# CommBoard.net
KiCad netlist of a schematic drawn in Altium Designer
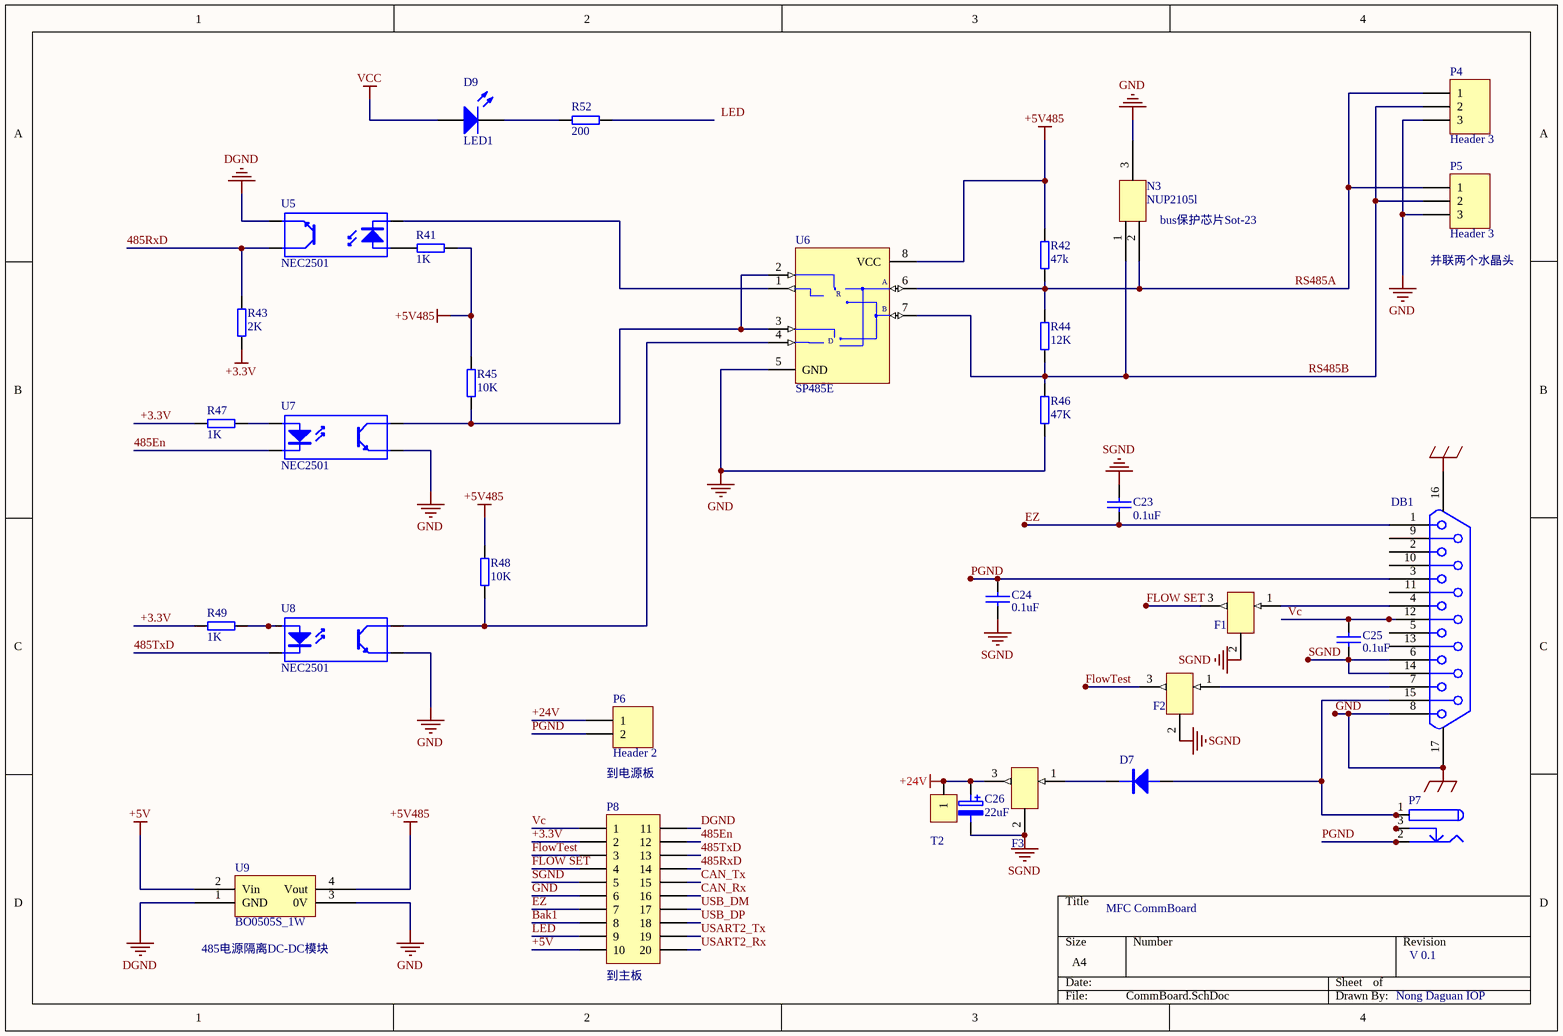
[diagram p0: CommBoard.SchDoc]

(export (version "E")
  (design (tool "Eeschema 10.0.6"))
  (components
    (comp (ref "C23") (value "0.1uF") (footprint "R.4") (libsource (lib "1.60") (part "CAP")))
    (comp (ref "C24") (value "0.1uF") (footprint "R.4") (libsource (lib "1.60") (part "CAP")))
    (comp (ref "C25") (value "0.1uF") (footprint "R.4") (libsource (lib "1.60") (part "CAP")))
    (comp (ref "C26") (value "22uF") (footprint "CA-22U") (libsource (lib "1.60") (part "ELECTRO2")))
    (comp (ref "D7") (value "2CK73C") (footprint "DIODE") (libsource (lib "1.60") (part "DIODE")))
    (comp (ref "D9")
      (value "LED1")
      (footprint "LED-1")
      (description "Typical RED GaAs LED")
      (fields (field (name "PUBLISHER") "Altium Limited"))
      (libsource (lib "Miscellaneous Devices") (part "LED1"))
    )
    (comp (ref "DB1") (value "DB15") (footprint "DB15RA/M") (libsource (lib "1.60") (part "DB15")))
    (comp (ref "F1") (value "TL-221M 100V") (footprint "FILTER") (libsource (lib "1.60") (part "FILTER")))
    (comp (ref "F2") (value "TL-221M 100V") (footprint "FILTER") (libsource (lib "1.60") (part "FILTER")))
    (comp (ref "F3") (value "TL-221M 100V") (footprint "FILTER") (libsource (lib "1.60") (part "FILTER")))
    (comp (ref "N3") (value "NUP2105l") (libsource (lib "1.60") (part "NUP2105l")))
    (comp (ref "P4")
      (value "Header 3")
      (footprint "HDR1X3")
      (description "Header, 3-Pin")
      (fields (field (name "PUBLISHER") "Altium Limited"))
      (libsource (lib "Miscellaneous Connectors") (part "Header 3"))
    )
    (comp (ref "P5")
      (value "Header 3")
      (footprint "HDR1X3")
      (description "Header, 3-Pin")
      (fields (field (name "PUBLISHER") "Altium Limited"))
      (libsource (lib "Miscellaneous Connectors") (part "Header 3"))
    )
    (comp (ref "P6")
      (value "Header 2")
      (footprint "HDR1X2")
      (description "Header, 2-Pin")
      (fields (field (name "PUBLISHER") "Altium Limited"))
      (libsource (lib "Miscellaneous Connectors") (part "Header 2"))
    )
    (comp (ref "P7")
      (value "~")
      (footprint "KLD-0202")
      (description "Low Voltage Power Supply Connector")
      (fields (field (name "PUBLISHER") "Altium Limited"))
      (libsource (lib "Miscellaneous Connectors") (part "PWR2.5"))
    )
    (comp (ref "P8")
      (value "~")
      (footprint "HDR2X10_CEN")
      (description "Header, 10-Pin, Dual row")
      (fields (field (name "PUBLISHER") "Altium Limited"))
      (libsource (lib "Miscellaneous Connectors") (part "Header 10X2A"))
    )
    (comp (ref "R41") (value "1K") (footprint "R.4") (libsource (lib "1.60") (part "RES_1")))
    (comp (ref "R42") (value "47k") (footprint "R.4") (libsource (lib "1.60") (part "RES_1")))
    (comp (ref "R43") (value "2K") (footprint "R.4") (libsource (lib "1.60") (part "RES_1")))
    (comp (ref "R44") (value "12K") (footprint "R.4") (libsource (lib "1.60") (part "RES_1")))
    (comp (ref "R45") (value "10K") (footprint "R.4") (libsource (lib "1.60") (part "RES_1")))
    (comp (ref "R46") (value "47K") (footprint "R.4") (libsource (lib "1.60") (part "RES_1")))
    (comp (ref "R47") (value "1K") (footprint "R.4") (libsource (lib "1.60") (part "RES_1")))
    (comp (ref "R48") (value "10K") (footprint "R.4") (libsource (lib "1.60") (part "RES_1")))
    (comp (ref "R49") (value "1K") (footprint "R.4") (libsource (lib "1.60") (part "RES_1")))
    (comp (ref "R52") (value "200") (footprint "R.4") (libsource (lib "1.60") (part "RES_1")))
    (comp (ref "T2") (value "CON1") (footprint "PAD - RECT") (libsource (lib "1.60") (part "CON1")))
    (comp (ref "U5")
      (value "NEC2501")
      (footprint "DIP-4")
      (description "4-Pin Phototransistor Optocoupler")
      (fields (field (name "PUBLISHER") "Altium Limited"))
      (libsource (lib "Miscellaneous Devices") (part "Optoisolator1"))
    )
    (comp (ref "U6")
      (value "SP485E")
      (footprint "SOT23-8")
      (description "MAX3362 3.3V, High-Speed, RS-485/RS-422 Transceiver in  SOT Package")
      (libsource (lib "AltiumDesignLibrary") (part "MAX3362"))
    )
    (comp (ref "U7")
      (value "NEC2501")
      (footprint "DIP-4")
      (description "4-Pin Phototransistor Optocoupler")
      (fields (field (name "PUBLISHER") "Altium Limited"))
      (libsource (lib "Miscellaneous Devices") (part "Optoisolator1"))
    )
    (comp (ref "U8")
      (value "NEC2501")
      (footprint "DIP-4")
      (description "4-Pin Phototransistor Optocoupler")
      (fields (field (name "PUBLISHER") "Altium Limited"))
      (libsource (lib "Miscellaneous Devices") (part "Optoisolator1"))
    )
    (comp (ref "U9") (value "BO0505S_1W") (libsource (lib "1.60") (part "BO0505S_1W")))
  )
  (nets
    (net (code "1") (name "+3.3V") (class "Default")
      (node (ref "P8") (pin "2") (pinfunction "2_2") (pintype "passive"))
      (node (ref "R43") (pin "1") (pintype "passive"))
      (node (ref "R47") (pin "1") (pintype "passive"))
      (node (ref "R49") (pin "1") (pintype "passive"))
    )
    (net (code "2") (name "+5V") (class "Default")
      (node (ref "P8") (pin "10") (pinfunction "10_10") (pintype "passive"))
      (node (ref "U9") (pin "2") (pinfunction "Vin_2") (pintype "passive"))
    )
    (net (code "3") (name "+5V485") (class "Default")
      (node (ref "R41") (pin "2") (pintype "passive"))
      (node (ref "R42") (pin "2") (pintype "passive"))
      (node (ref "R45") (pin "2") (pintype "passive"))
      (node (ref "R48") (pin "2") (pintype "passive"))
      (node (ref "U6") (pin "8") (pinfunction "VCC_8") (pintype "power_in"))
      (node (ref "U9") (pin "4") (pinfunction "Vout_4") (pintype "passive"))
    )
    (net (code "4") (name "+24V") (class "Default")
      (node (ref "C26") (pin "1") (pintype "passive"))
      (node (ref "F3") (pin "3") (pinfunction "OUT_3") (pintype "output"))
      (node (ref "P6") (pin "1") (pinfunction "1_1") (pintype "passive"))
      (node (ref "T2") (pin "1") (pinfunction "1_1") (pintype "passive"))
    )
    (net (code "5") (name "/485En") (class "Default")
      (node (ref "P8") (pin "12") (pinfunction "12_12") (pintype "passive"))
      (node (ref "U7") (pin "2") (pinfunction "K_2") (pintype "passive"))
    )
    (net (code "6") (name "/485RxD") (class "Default")
      (node (ref "P8") (pin "14") (pinfunction "14_14") (pintype "passive"))
      (node (ref "R43") (pin "2") (pintype "passive"))
      (node (ref "U5") (pin "4") (pinfunction "C_4") (pintype "passive"))
    )
    (net (code "7") (name "/485TxD") (class "Default")
      (node (ref "P8") (pin "13") (pinfunction "13_13") (pintype "passive"))
      (node (ref "U8") (pin "2") (pinfunction "K_2") (pintype "passive"))
    )
    (net (code "8") (name "/Bak1") (class "Default")
      (node (ref "P8") (pin "8") (pinfunction "8_8") (pintype "passive"))
    )
    (net (code "9") (name "/CAN_Rx") (class "Default")
      (node (ref "P8") (pin "16") (pinfunction "16_16") (pintype "passive"))
    )
    (net (code "10") (name "/CAN_Tx") (class "Default")
      (node (ref "P8") (pin "15") (pinfunction "15_15") (pintype "passive"))
    )
    (net (code "11") (name "/EZ") (class "Default")
      (node (ref "C23") (pin "1") (pintype "passive"))
      (node (ref "DB1") (pin "1") (pintype "passive"))
      (node (ref "P8") (pin "7") (pinfunction "7_7") (pintype "passive"))
    )
    (net (code "12") (name "/FLOW SET") (class "Default")
      (node (ref "F1") (pin "3") (pinfunction "OUT_3") (pintype "output"))
      (node (ref "P8") (pin "4") (pinfunction "4_4") (pintype "passive"))
    )
    (net (code "13") (name "/FlowTest") (class "Default")
      (node (ref "F2") (pin "3") (pinfunction "OUT_3") (pintype "output"))
      (node (ref "P8") (pin "3") (pinfunction "3_3") (pintype "passive"))
    )
    (net (code "14") (name "/LED") (class "Default")
      (node (ref "P8") (pin "9") (pinfunction "9_9") (pintype "passive"))
    )
    (net (code "15") (name "/PGND") (class "Default")
      (node (ref "C24") (pin "2") (pintype "passive"))
      (node (ref "DB1") (pin "3") (pintype "passive"))
      (node (ref "P6") (pin "2") (pinfunction "2_2") (pintype "passive"))
      (node (ref "P7") (pin "2") (pinfunction "2_2") (pintype "power_in"))
      (node (ref "P7") (pin "2A") (pinfunction "2A_2A") (pintype "power_in"))
      (node (ref "P7") (pin "2B") (pinfunction "2B_2B") (pintype "power_in"))
    )
    (net (code "16") (name "/RS485A") (class "Default")
      (node (ref "N3") (pin "2") (pinfunction "2_2") (pintype "passive"))
      (node (ref "P4") (pin "1") (pinfunction "1_1") (pintype "passive"))
      (node (ref "P5") (pin "1") (pinfunction "1_1") (pintype "passive"))
      (node (ref "R42") (pin "1") (pintype "passive"))
      (node (ref "R44") (pin "2") (pintype "passive"))
      (node (ref "U6") (pin "6") (pinfunction "A_6") (pintype "bidirectional"))
    )
    (net (code "17") (name "/RS485B") (class "Default")
      (node (ref "N3") (pin "1") (pinfunction "1_1") (pintype "passive"))
      (node (ref "P4") (pin "2") (pinfunction "2_2") (pintype "passive"))
      (node (ref "P5") (pin "2") (pinfunction "2_2") (pintype "passive"))
      (node (ref "R44") (pin "1") (pintype "passive"))
      (node (ref "R46") (pin "2") (pintype "passive"))
      (node (ref "U6") (pin "7") (pinfunction "B_7") (pintype "bidirectional"))
    )
    (net (code "18") (name "/USART2_Rx") (class "Default")
      (node (ref "P8") (pin "20") (pinfunction "20_20") (pintype "passive"))
    )
    (net (code "19") (name "/USART2_Tx") (class "Default")
      (node (ref "P8") (pin "19") (pinfunction "19_19") (pintype "passive"))
    )
    (net (code "20") (name "/USB_DM") (class "Default")
      (node (ref "P8") (pin "17") (pinfunction "17_17") (pintype "passive"))
    )
    (net (code "21") (name "/USB_DP") (class "Default")
      (node (ref "P8") (pin "18") (pinfunction "18_18") (pintype "passive"))
    )
    (net (code "22") (name "/Vc") (class "Default")
      (node (ref "C25") (pin "2") (pintype "passive"))
      (node (ref "DB1") (pin "12") (pintype "passive"))
      (node (ref "P8") (pin "1") (pinfunction "1_1") (pintype "passive"))
    )
    (net (code "23") (name "DGND") (class "Default")
      (node (ref "P8") (pin "11") (pinfunction "11_11") (pintype "passive"))
      (node (ref "U5") (pin "3") (pinfunction "E_3") (pintype "passive"))
      (node (ref "U9") (pin "1") (pinfunction "GND_1") (pintype "passive"))
    )
    (net (code "24") (name "GND") (class "Default")
      (node (ref "DB1") (pin "16") (pinfunction "Pad_16") (pintype "passive"))
      (node (ref "DB1") (pin "17") (pinfunction "Pad_17") (pintype "passive"))
      (node (ref "DB1") (pin "8") (pintype "passive"))
      (node (ref "N3") (pin "3") (pinfunction "3_3") (pintype "passive"))
      (node (ref "P4") (pin "3") (pinfunction "3_3") (pintype "passive"))
      (node (ref "P5") (pin "3") (pinfunction "3_3") (pintype "passive"))
      (node (ref "P8") (pin "6") (pinfunction "6_6") (pintype "passive"))
      (node (ref "R46") (pin "1") (pintype "passive"))
      (node (ref "U6") (pin "5") (pinfunction "GND_5") (pintype "power_in"))
      (node (ref "U7") (pin "3") (pinfunction "E_3") (pintype "passive"))
      (node (ref "U8") (pin "3") (pinfunction "E_3") (pintype "passive"))
      (node (ref "U9") (pin "3") (pinfunction "0V_3") (pintype "passive"))
    )
    (net (code "25") (name "Net-(D7-PadA)") (class "Default")
      (node (ref "D7") (pin "A") (pintype "passive"))
      (node (ref "DB1") (pin "15") (pintype "passive"))
      (node (ref "P7") (pin "1") (pinfunction "1_1") (pintype "power_in"))
      (node (ref "P7") (pin "1A") (pinfunction "1A_1A") (pintype "power_in"))
      (node (ref "P7") (pin "1B") (pinfunction "1B_1B") (pintype "power_in"))
    )
    (net (code "26") (name "Net-(D9-K)") (class "Default")
      (node (ref "D9") (pin "2") (pinfunction "K_2") (pintype "passive"))
      (node (ref "R52") (pin "1") (pintype "passive"))
    )
    (net (code "27") (name "Net-(F1-IN)") (class "Default")
      (node (ref "DB1") (pin "4") (pintype "passive"))
      (node (ref "F1") (pin "1") (pinfunction "IN_1") (pintype "input"))
    )
    (net (code "28") (name "Net-(F2-IN)") (class "Default")
      (node (ref "DB1") (pin "7") (pintype "passive"))
      (node (ref "F2") (pin "1") (pinfunction "IN_1") (pintype "input"))
    )
    (net (code "29") (name "Net-(F3-IN)") (class "Default")
      (node (ref "D7") (pin "K") (pintype "passive"))
      (node (ref "F3") (pin "1") (pinfunction "IN_1") (pintype "input"))
    )
    (net (code "30") (name "Net-(P7-Pad3)") (class "Default")
      (node (ref "P7") (pin "3") (pinfunction "3_3") (pintype "power_in"))
      (node (ref "P7") (pin "3A") (pinfunction "3A_3A") (pintype "power_in"))
      (node (ref "P7") (pin "3B") (pinfunction "3B_3B") (pintype "power_in"))
    )
    (net (code "31") (name "Net-(U5-A)") (class "Default")
      (node (ref "R41") (pin "1") (pintype "passive"))
      (node (ref "U5") (pin "1") (pinfunction "A_1") (pintype "passive"))
    )
    (net (code "32") (name "Net-(U5-K)") (class "Default")
      (node (ref "U5") (pin "2") (pinfunction "K_2") (pintype "passive"))
      (node (ref "U6") (pin "1") (pinfunction "RO_1") (pintype "output"))
    )
    (net (code "33") (name "Net-(U6-DE)") (class "Default")
      (node (ref "R45") (pin "1") (pintype "passive"))
      (node (ref "U6") (pin "2") (pinfunction "~{RE}_2") (pintype "input"))
      (node (ref "U6") (pin "3") (pinfunction "DE_3") (pintype "input"))
      (node (ref "U7") (pin "4") (pinfunction "C_4") (pintype "passive"))
    )
    (net (code "34") (name "Net-(U6-DI)") (class "Default")
      (node (ref "R48") (pin "1") (pintype "passive"))
      (node (ref "U6") (pin "4") (pinfunction "DI_4") (pintype "input"))
      (node (ref "U8") (pin "4") (pinfunction "C_4") (pintype "passive"))
    )
    (net (code "35") (name "Net-(U7-A)") (class "Default")
      (node (ref "R47") (pin "2") (pintype "passive"))
      (node (ref "U7") (pin "1") (pinfunction "A_1") (pintype "passive"))
    )
    (net (code "36") (name "Net-(U8-A)") (class "Default")
      (node (ref "R49") (pin "2") (pintype "passive"))
      (node (ref "U8") (pin "1") (pinfunction "A_1") (pintype "passive"))
    )
    (net (code "37") (name "SGND") (class "Default")
      (node (ref "C23") (pin "2") (pintype "passive"))
      (node (ref "C24") (pin "1") (pintype "passive"))
      (node (ref "C25") (pin "1") (pintype "passive"))
      (node (ref "C26") (pin "2") (pintype "passive"))
      (node (ref "DB1") (pin "14") (pintype "passive"))
      (node (ref "DB1") (pin "6") (pintype "passive"))
      (node (ref "F1") (pin "2") (pinfunction "GND_2") (pintype "power_in"))
      (node (ref "F2") (pin "2") (pinfunction "GND_2") (pintype "power_in"))
      (node (ref "F3") (pin "2") (pinfunction "GND_2") (pintype "power_in"))
      (node (ref "P8") (pin "5") (pinfunction "5_5") (pintype "passive"))
    )
    (net (code "38") (name "VCC") (class "Default")
      (node (ref "D9") (pin "1") (pinfunction "A_1") (pintype "passive"))
    )
    (net (code "39") (name "unconnected-(DB1-Pad2)") (class "Default")
      (node (ref "DB1") (pin "2") (pintype "passive"))
    )
    (net (code "40") (name "unconnected-(DB1-Pad5)") (class "Default")
      (node (ref "DB1") (pin "5") (pintype "passive"))
    )
    (net (code "41") (name "unconnected-(DB1-Pad9)") (class "Default")
      (node (ref "DB1") (pin "9") (pintype "passive"))
    )
    (net (code "42") (name "unconnected-(DB1-Pad10)") (class "Default")
      (node (ref "DB1") (pin "10") (pintype "passive"))
    )
    (net (code "43") (name "unconnected-(DB1-Pad11)") (class "Default")
      (node (ref "DB1") (pin "11") (pintype "passive"))
    )
    (net (code "44") (name "unconnected-(DB1-Pad13)") (class "Default")
      (node (ref "DB1") (pin "13") (pintype "passive"))
    )
    (net (code "45") (name "unconnected-(R52-Pad2)") (class "Default")
      (node (ref "R52") (pin "2") (pintype "passive"))
    )
  )
)
